# USB.net
KiCad netlist of a schematic drawn in Altium Designer
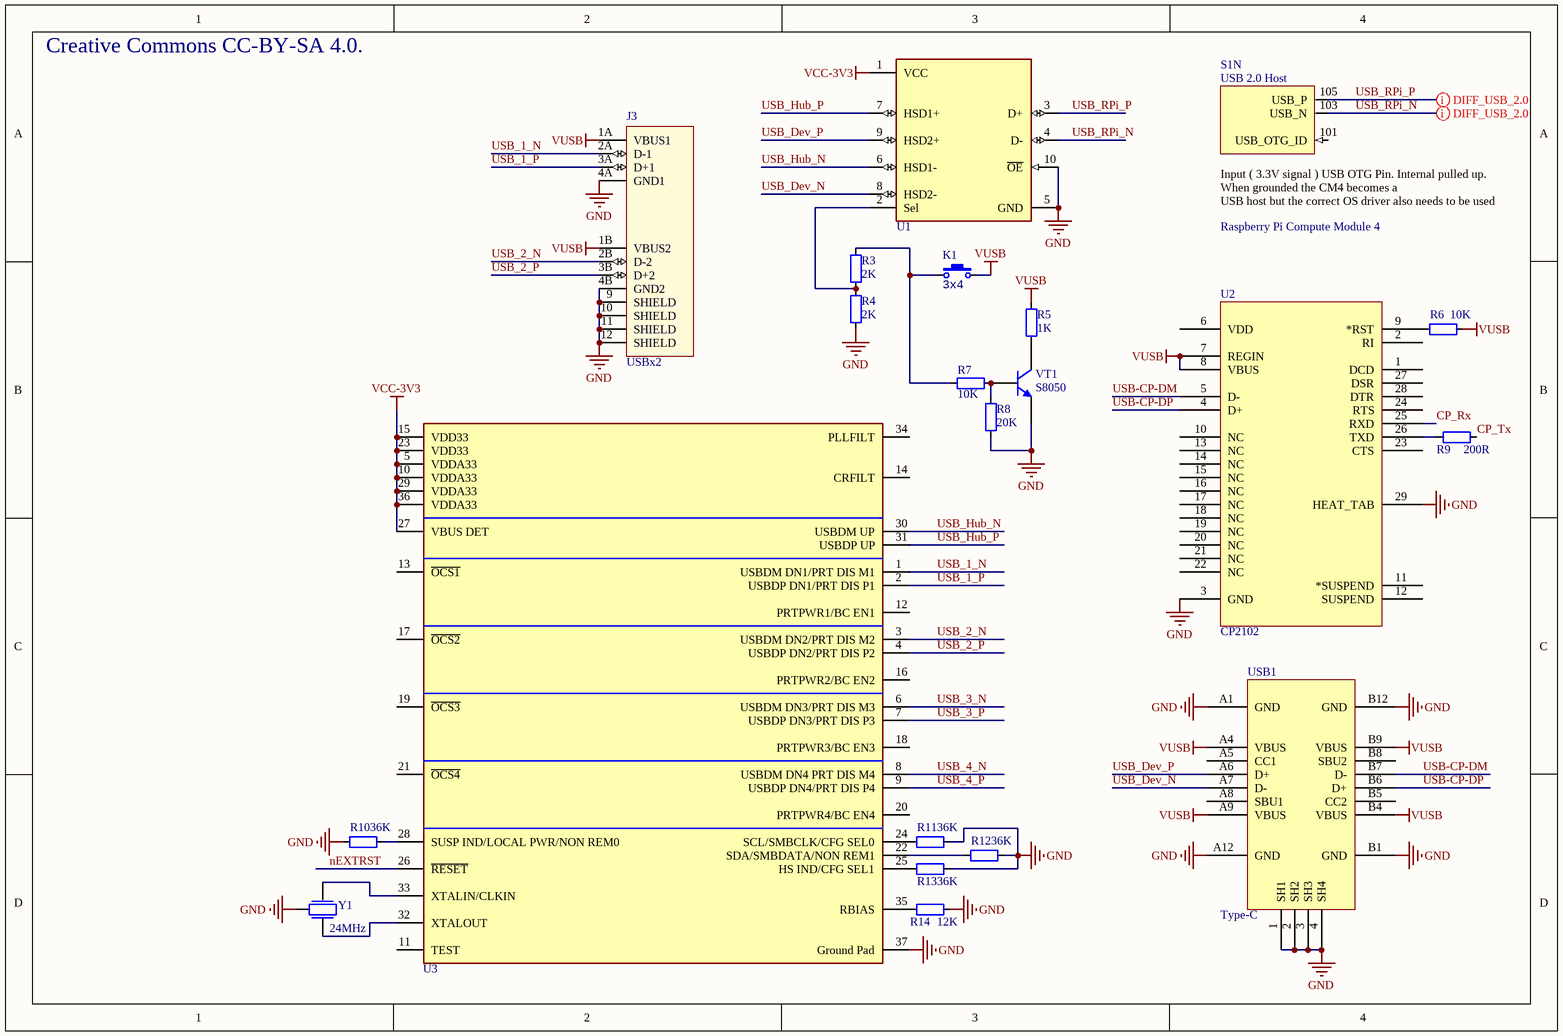
[diagram p0: USB.SchDoc]

(export (version "E")
  (design (tool "Eeschema 10.0.6"))
  (components
    (comp (ref "J3")
      (value "USBx2")
      (footprint "USBx2")
      (description "Usb Conn, Dual Rcpt, 2.0, 2port, 8pos")
      (fields (field (name "MF") "Global Connector Technology") (field (name "MP") "USB1035-GF-P-0-B-B"))
      (libsource (lib "MyPcbLib") (part "USBx2"))
    )
    (comp (ref "K1")
      (value "3x4")
      (footprint "ButtonTACT_3x4x2_180H")
      (description "Button")
      (fields (field (name "Comment") "TACT 2P"))
      (libsource (lib "KitSprout") (part "ButtonTACT_3x4x2_180"))
    )
    (comp (ref "R3")
      (value "2K")
      (footprint "RES_0402")
      (description "Resistor")
      (libsource (lib "MyPcbLib") (part "电阻-0402"))
    )
    (comp (ref "R4")
      (value "2K")
      (footprint "RES_0402")
      (description "Resistor")
      (libsource (lib "MyPcbLib") (part "电阻-0402"))
    )
    (comp (ref "R5")
      (value "1K")
      (footprint "RES_0402")
      (description "Resistor")
      (libsource (lib "MyPcbLib") (part "电阻-0402"))
    )
    (comp (ref "R6")
      (value "10K")
      (footprint "RES_0402")
      (description "Resistor")
      (libsource (lib "") (part "电阻-0402_1"))
    )
    (comp (ref "R7")
      (value "10K")
      (footprint "RES_0402")
      (description "Resistor")
      (libsource (lib "") (part "电阻-0402_2"))
    )
    (comp (ref "R8")
      (value "20K")
      (footprint "RES_0402")
      (description "Resistor")
      (libsource (lib "") (part "电阻-0402_3"))
    )
    (comp (ref "R9")
      (value "200R")
      (footprint "RES_0402")
      (description "Resistor")
      (libsource (lib "") (part "电阻-0402_1"))
    )
    (comp (ref "R10")
      (value "36K")
      (footprint "RES_0402")
      (description "Resistor")
      (libsource (lib "") (part "电阻-0402_1"))
    )
    (comp (ref "R11")
      (value "36K")
      (footprint "RES_0402")
      (description "Resistor")
      (libsource (lib "") (part "电阻-0402_1"))
    )
    (comp (ref "R12")
      (value "36K")
      (footprint "RES_0402")
      (description "Resistor")
      (libsource (lib "") (part "电阻-0402_1"))
    )
    (comp (ref "R13")
      (value "36K")
      (footprint "RES_0402")
      (description "Resistor")
      (libsource (lib "") (part "电阻-0402_1"))
    )
    (comp (ref "R14")
      (value "12K")
      (footprint "RES_0402")
      (description "Resistor")
      (libsource (lib "") (part "电阻-0402_1"))
    )
    (comp (ref "S1")
      (value "Raspberry Pi Compute Module 4")
      (footprint "CM4-F40C-100DS-0.4v_1.5mm_0mm")
      (description "Raspberry Pi Compute Module 4 by Amornthep Phunsin")
      (libsource (lib "SOM") (part "CM4"))
    )
    (comp (ref "U1")
      (value "FSUSB42MUX")
      (footprint "MSOP-10")
      (libsource (lib "MyPcbLib") (part "FSUSB42MUX"))
    )
    (comp (ref "U2")
      (value "CP2102")
      (footprint "QFN-28")
      (description "USB转TTL")
      (libsource (lib "mLib") (part "CP2102"))
    )
    (comp (ref "U3")
      (value "USB2514BT-I-M2")
      (footprint "QFN-36")
      (libsource (lib "MyPcbLib") (part "USB2514BT-I-M2"))
    )
    (comp (ref "USB1")
      (value "Type-C")
      (footprint "Type-C-TOP")
      (libsource (lib "MyPcbLib") (part "USB-Type-C-TOP"))
    )
    (comp (ref "VT1")
      (value "S8050")
      (footprint "SMT_TRIODE_NPN")
      (description "Surface mount NPN transistor, package SOT-23")
      (libsource (lib "MyPcbLib") (part "SMT_TRIODE_NPN"))
    )
    (comp (ref "Y1")
      (value "24MHz")
      (footprint "晶振-3P")
      (description "村田贴片")
      (libsource (lib "MyPcbLib") (part "晶振-3Pin"))
    )
  )
  (nets
    (net (code "1") (name "/CP_Rx") (class "Default")
      (node (ref "U2") (pin "25") (pinfunction "RXD_25") (pintype "passive"))
    )
    (net (code "2") (name "/CP_Tx") (class "Default")
      (node (ref "R9") (pin "1") (pinfunction "1_1") (pintype "passive"))
    )
    (net (code "3") (name "/USB-CP-DM") (class "Default")
      (node (ref "U2") (pin "5") (pinfunction "D-_5") (pintype "passive"))
      (node (ref "USB1") (pin "B7") (pinfunction "D-_B7") (pintype "passive"))
    )
    (net (code "4") (name "/USB-CP-DP") (class "Default")
      (node (ref "U2") (pin "4") (pinfunction "D+_4") (pintype "passive"))
      (node (ref "USB1") (pin "B6") (pinfunction "D+_B6") (pintype "passive"))
    )
    (net (code "5") (name "/USB_1_N") (class "Default")
      (node (ref "J3") (pin "2A") (pinfunction "D-1_2A") (pintype "bidirectional"))
      (node (ref "U3") (pin "1") (pinfunction "USBDM_DN1/PRT_DIS_M1_1") (pintype "passive"))
    )
    (net (code "6") (name "/USB_1_P") (class "Default")
      (node (ref "J3") (pin "3A") (pinfunction "D+1_3A") (pintype "bidirectional"))
      (node (ref "U3") (pin "2") (pinfunction "USBDP_DN1/PRT_DIS_P1_2") (pintype "passive"))
    )
    (net (code "7") (name "/USB_2_N") (class "Default")
      (node (ref "J3") (pin "2B") (pinfunction "D-2_2B") (pintype "bidirectional"))
      (node (ref "U3") (pin "3") (pinfunction "USBDM_DN2/PRT_DIS_M2_3") (pintype "passive"))
    )
    (net (code "8") (name "/USB_2_P") (class "Default")
      (node (ref "J3") (pin "3B") (pinfunction "D+2_3B") (pintype "bidirectional"))
      (node (ref "U3") (pin "4") (pinfunction "USBDP_DN2/PRT_DIS_P2_4") (pintype "passive"))
    )
    (net (code "9") (name "/USB_3_N") (class "Default")
      (node (ref "U3") (pin "6") (pinfunction "USBDM_DN3/PRT_DIS_M3_6") (pintype "passive"))
    )
    (net (code "10") (name "/USB_3_P") (class "Default")
      (node (ref "U3") (pin "7") (pinfunction "USBDP_DN3/PRT_DIS_P3_7") (pintype "passive"))
    )
    (net (code "11") (name "/USB_4_N") (class "Default")
      (node (ref "U3") (pin "8") (pinfunction "USBDM_DN4_PRT_DIS_M4_8") (pintype "passive"))
    )
    (net (code "12") (name "/USB_4_P") (class "Default")
      (node (ref "U3") (pin "9") (pinfunction "USBDP_DN4/PRT_DIS_P4_9") (pintype "passive"))
    )
    (net (code "13") (name "/USB_Dev_N") (class "Default")
      (node (ref "U1") (pin "8") (pinfunction "HSD2-_8") (pintype "bidirectional"))
      (node (ref "USB1") (pin "A7") (pinfunction "D-_A7") (pintype "passive"))
    )
    (net (code "14") (name "/USB_Dev_P") (class "Default")
      (node (ref "U1") (pin "9") (pinfunction "HSD2+_9") (pintype "bidirectional"))
      (node (ref "USB1") (pin "A6") (pinfunction "D+_A6") (pintype "passive"))
    )
    (net (code "15") (name "/USB_Hub_N") (class "Default")
      (node (ref "U1") (pin "6") (pinfunction "HSD1-_6") (pintype "bidirectional"))
      (node (ref "U3") (pin "30") (pinfunction "USBDM_UP_30") (pintype "passive"))
    )
    (net (code "16") (name "/USB_Hub_P") (class "Default")
      (node (ref "U1") (pin "7") (pinfunction "HSD1+_7") (pintype "bidirectional"))
      (node (ref "U3") (pin "31") (pinfunction "USBDP_UP_31") (pintype "passive"))
    )
    (net (code "17") (name "/USB_RPi_N") (class "Default")
      (node (ref "S1") (pin "103") (pinfunction "USB_N_103") (pintype "passive"))
      (node (ref "U1") (pin "4") (pinfunction "D-_4") (pintype "bidirectional"))
    )
    (net (code "18") (name "/USB_RPi_P") (class "Default")
      (node (ref "S1") (pin "105") (pinfunction "USB_P_105") (pintype "passive"))
      (node (ref "U1") (pin "3") (pinfunction "D+_3") (pintype "bidirectional"))
    )
    (net (code "19") (name "/nEXTRST") (class "Default")
      (node (ref "U3") (pin "26") (pinfunction "~{RESET}_26") (pintype "passive"))
    )
    (net (code "20") (name "GND") (class "Default")
      (node (ref "J3") (pin "10") (pinfunction "SHIELD_10") (pintype "power_in"))
      (node (ref "J3") (pin "11") (pinfunction "SHIELD_11") (pintype "power_in"))
      (node (ref "J3") (pin "12") (pinfunction "SHIELD_12") (pintype "power_in"))
      (node (ref "J3") (pin "4A") (pinfunction "GND1_4A") (pintype "power_in"))
      (node (ref "J3") (pin "4B") (pinfunction "GND2_4B") (pintype "power_in"))
      (node (ref "J3") (pin "9") (pinfunction "SHIELD_9") (pintype "power_in"))
      (node (ref "R10") (pin "2") (pinfunction "2_2") (pintype "passive"))
      (node (ref "R11") (pin "1") (pinfunction "1_1") (pintype "passive"))
      (node (ref "R12") (pin "1") (pinfunction "1_1") (pintype "passive"))
      (node (ref "R13") (pin "1") (pinfunction "1_1") (pintype "passive"))
      (node (ref "R14") (pin "1") (pinfunction "1_1") (pintype "passive"))
      (node (ref "R4") (pin "2") (pinfunction "2_2") (pintype "passive"))
      (node (ref "R8") (pin "1") (pinfunction "1_1") (pintype "passive"))
      (node (ref "U1") (pin "10") (pinfunction "~{OE}_10") (pintype "input"))
      (node (ref "U1") (pin "5") (pinfunction "GND_5") (pintype "power_in"))
      (node (ref "U2") (pin "29") (pinfunction "HEAT_TAB_29") (pintype "passive"))
      (node (ref "U2") (pin "3") (pinfunction "GND_3") (pintype "passive"))
      (node (ref "U3") (pin "37") (pinfunction "Ground_Pad_37") (pintype "passive"))
      (node (ref "USB1") (pin "1") (pinfunction "SH1_1") (pintype "passive"))
      (node (ref "USB1") (pin "2") (pinfunction "SH2_2") (pintype "passive"))
      (node (ref "USB1") (pin "3") (pinfunction "SH3_3") (pintype "passive"))
      (node (ref "USB1") (pin "4") (pinfunction "SH4_4") (pintype "passive"))
      (node (ref "USB1") (pin "A1") (pinfunction "GND_A1") (pintype "passive"))
      (node (ref "USB1") (pin "A12") (pinfunction "GND_A12") (pintype "passive"))
      (node (ref "USB1") (pin "B1") (pinfunction "GND_B1") (pintype "passive"))
      (node (ref "USB1") (pin "B12") (pinfunction "GND_B12") (pintype "passive"))
      (node (ref "VT1") (pin "2") (pinfunction "E_2") (pintype "passive"))
      (node (ref "Y1") (pin "2") (pinfunction "2_2") (pintype "passive"))
    )
    (net (code "21") (name "Net-(K1-Pad1)") (class "Default")
      (node (ref "K1") (pin "1") (pinfunction "1_1") (pintype "passive"))
      (node (ref "R3") (pin "1") (pinfunction "1_1") (pintype "passive"))
      (node (ref "R7") (pin "1") (pinfunction "1_1") (pintype "passive"))
    )
    (net (code "22") (name "Net-(U1-Sel)") (class "Default")
      (node (ref "R3") (pin "2") (pinfunction "2_2") (pintype "passive"))
      (node (ref "R4") (pin "1") (pinfunction "1_1") (pintype "passive"))
      (node (ref "U1") (pin "2") (pinfunction "Sel_2") (pintype "passive"))
    )
    (net (code "23") (name "Net-(U2-*RST)") (class "Default")
      (node (ref "R6") (pin "2") (pinfunction "2_2") (pintype "passive"))
      (node (ref "U2") (pin "9") (pinfunction "*RST_9") (pintype "passive"))
    )
    (net (code "24") (name "Net-(U2-TXD)") (class "Default")
      (node (ref "R9") (pin "2") (pinfunction "2_2") (pintype "passive"))
      (node (ref "U2") (pin "26") (pinfunction "TXD_26") (pintype "passive"))
    )
    (net (code "25") (name "Net-(U3-HS_IND{slash}CFG_SEL1)") (class "Default")
      (node (ref "R13") (pin "2") (pinfunction "2_2") (pintype "passive"))
      (node (ref "U3") (pin "25") (pinfunction "HS_IND/CFG_SEL1_25") (pintype "passive"))
    )
    (net (code "26") (name "Net-(U3-RBIAS)") (class "Default")
      (node (ref "R14") (pin "2") (pinfunction "2_2") (pintype "passive"))
      (node (ref "U3") (pin "35") (pinfunction "RBIAS_35") (pintype "passive"))
    )
    (net (code "27") (name "Net-(U3-SCL{slash}SMBCLK{slash}CFG_SEL0)") (class "Default")
      (node (ref "R11") (pin "2") (pinfunction "2_2") (pintype "passive"))
      (node (ref "U3") (pin "24") (pinfunction "SCL/SMBCLK/CFG_SEL0_24") (pintype "passive"))
    )
    (net (code "28") (name "Net-(U3-SDA{slash}SMBDATA{slash}NON_REM1)") (class "Default")
      (node (ref "R12") (pin "2") (pinfunction "2_2") (pintype "passive"))
      (node (ref "U3") (pin "22") (pinfunction "SDA/SMBDATA/NON_REM1_22") (pintype "passive"))
    )
    (net (code "29") (name "Net-(U3-SUSP_IND{slash}LOCAL_PWR{slash}NON_REM0)") (class "Default")
      (node (ref "R10") (pin "1") (pinfunction "1_1") (pintype "passive"))
      (node (ref "U3") (pin "28") (pinfunction "SUSP_IND/LOCAL_PWR/NON_REM0_28") (pintype "passive"))
    )
    (net (code "30") (name "Net-(U3-XTALIN{slash}CLKIN)") (class "Default")
      (node (ref "U3") (pin "33") (pinfunction "XTALIN/CLKIN_33") (pintype "passive"))
      (node (ref "Y1") (pin "3") (pinfunction "3_3") (pintype "passive"))
    )
    (net (code "31") (name "Net-(U3-XTALOUT)") (class "Default")
      (node (ref "U3") (pin "32") (pinfunction "XTALOUT_32") (pintype "passive"))
      (node (ref "Y1") (pin "1") (pinfunction "1_1") (pintype "passive"))
    )
    (net (code "32") (name "Net-(VT1-B)") (class "Default")
      (node (ref "R7") (pin "2") (pinfunction "2_2") (pintype "passive"))
      (node (ref "R8") (pin "2") (pinfunction "2_2") (pintype "passive"))
      (node (ref "VT1") (pin "1") (pinfunction "B_1") (pintype "passive"))
    )
    (net (code "33") (name "Net-(VT1-C)") (class "Default")
      (node (ref "R5") (pin "2") (pinfunction "2_2") (pintype "passive"))
      (node (ref "VT1") (pin "3") (pinfunction "C_3") (pintype "passive"))
    )
    (net (code "34") (name "VCC-3V3") (class "Default")
      (node (ref "U1") (pin "1") (pinfunction "VCC_1") (pintype "power_in"))
      (node (ref "U3") (pin "10") (pinfunction "VDDA33_10") (pintype "passive"))
      (node (ref "U3") (pin "15") (pinfunction "VDD33_15") (pintype "passive"))
      (node (ref "U3") (pin "23") (pinfunction "VDD33_23") (pintype "passive"))
      (node (ref "U3") (pin "27") (pinfunction "VBUS_DET_27") (pintype "passive"))
      (node (ref "U3") (pin "29") (pinfunction "VDDA33_29") (pintype "passive"))
      (node (ref "U3") (pin "36") (pinfunction "VDDA33_36") (pintype "passive"))
      (node (ref "U3") (pin "5") (pinfunction "VDDA33_5") (pintype "passive"))
    )
    (net (code "35") (name "VUSB") (class "Default")
      (node (ref "J3") (pin "1A") (pinfunction "VBUS1_1A") (pintype "power_in"))
      (node (ref "J3") (pin "1B") (pinfunction "VBUS2_1B") (pintype "power_in"))
      (node (ref "K1") (pin "2") (pinfunction "2_2") (pintype "passive"))
      (node (ref "R5") (pin "1") (pinfunction "1_1") (pintype "passive"))
      (node (ref "R6") (pin "1") (pinfunction "1_1") (pintype "passive"))
      (node (ref "U2") (pin "7") (pinfunction "REGIN_7") (pintype "passive"))
      (node (ref "U2") (pin "8") (pinfunction "VBUS_8") (pintype "passive"))
      (node (ref "USB1") (pin "A4") (pinfunction "VBUS_A4") (pintype "passive"))
      (node (ref "USB1") (pin "A9") (pinfunction "VBUS_A9") (pintype "passive"))
      (node (ref "USB1") (pin "B4") (pinfunction "VBUS_B4") (pintype "passive"))
      (node (ref "USB1") (pin "B9") (pinfunction "VBUS_B9") (pintype "passive"))
    )
    (net (code "36") (name "unconnected-(S1N-USB_OTG_ID-Pad101)") (class "Default")
      (node (ref "S1") (pin "101") (pinfunction "USB_OTG_ID_101") (pintype "input"))
    )
    (net (code "37") (name "unconnected-(U2-*SUSPEND-Pad11)") (class "Default")
      (node (ref "U2") (pin "11") (pinfunction "*SUSPEND_11") (pintype "passive"))
    )
    (net (code "38") (name "unconnected-(U2-CTS-Pad23)") (class "Default")
      (node (ref "U2") (pin "23") (pinfunction "CTS_23") (pintype "passive"))
    )
    (net (code "39") (name "unconnected-(U2-DCD-Pad1)") (class "Default")
      (node (ref "U2") (pin "1") (pinfunction "DCD_1") (pintype "passive"))
    )
    (net (code "40") (name "unconnected-(U2-DSR-Pad27)") (class "Default")
      (node (ref "U2") (pin "27") (pinfunction "DSR_27") (pintype "passive"))
    )
    (net (code "41") (name "unconnected-(U2-DTR-Pad28)") (class "Default")
      (node (ref "U2") (pin "28") (pinfunction "DTR_28") (pintype "passive"))
    )
    (net (code "42") (name "unconnected-(U2-NC-Pad10)") (class "Default")
      (node (ref "U2") (pin "10") (pinfunction "NC_10") (pintype "passive"))
    )
    (net (code "43") (name "unconnected-(U2-NC-Pad13)") (class "Default")
      (node (ref "U2") (pin "13") (pinfunction "NC_13") (pintype "passive"))
    )
    (net (code "44") (name "unconnected-(U2-NC-Pad14)") (class "Default")
      (node (ref "U2") (pin "14") (pinfunction "NC_14") (pintype "passive"))
    )
    (net (code "45") (name "unconnected-(U2-NC-Pad15)") (class "Default")
      (node (ref "U2") (pin "15") (pinfunction "NC_15") (pintype "passive"))
    )
    (net (code "46") (name "unconnected-(U2-NC-Pad16)") (class "Default")
      (node (ref "U2") (pin "16") (pinfunction "NC_16") (pintype "passive"))
    )
    (net (code "47") (name "unconnected-(U2-NC-Pad17)") (class "Default")
      (node (ref "U2") (pin "17") (pinfunction "NC_17") (pintype "passive"))
    )
    (net (code "48") (name "unconnected-(U2-NC-Pad18)") (class "Default")
      (node (ref "U2") (pin "18") (pinfunction "NC_18") (pintype "passive"))
    )
    (net (code "49") (name "unconnected-(U2-NC-Pad19)") (class "Default")
      (node (ref "U2") (pin "19") (pinfunction "NC_19") (pintype "passive"))
    )
    (net (code "50") (name "unconnected-(U2-NC-Pad20)") (class "Default")
      (node (ref "U2") (pin "20") (pinfunction "NC_20") (pintype "passive"))
    )
    (net (code "51") (name "unconnected-(U2-NC-Pad21)") (class "Default")
      (node (ref "U2") (pin "21") (pinfunction "NC_21") (pintype "passive"))
    )
    (net (code "52") (name "unconnected-(U2-NC-Pad22)") (class "Default")
      (node (ref "U2") (pin "22") (pinfunction "NC_22") (pintype "passive"))
    )
    (net (code "53") (name "unconnected-(U2-RI-Pad2)") (class "Default")
      (node (ref "U2") (pin "2") (pinfunction "RI_2") (pintype "passive"))
    )
    (net (code "54") (name "unconnected-(U2-RTS-Pad24)") (class "Default")
      (node (ref "U2") (pin "24") (pinfunction "RTS_24") (pintype "passive"))
    )
    (net (code "55") (name "unconnected-(U2-SUSPEND-Pad12)") (class "Default")
      (node (ref "U2") (pin "12") (pinfunction "SUSPEND_12") (pintype "passive"))
    )
    (net (code "56") (name "unconnected-(U2-VDD-Pad6)") (class "Default")
      (node (ref "U2") (pin "6") (pinfunction "VDD_6") (pintype "passive"))
    )
    (net (code "57") (name "unconnected-(U3-CRFILT-Pad14)") (class "Default")
      (node (ref "U3") (pin "14") (pinfunction "CRFILT_14") (pintype "passive"))
    )
    (net (code "58") (name "unconnected-(U3-PLLFILT-Pad34)") (class "Default")
      (node (ref "U3") (pin "34") (pinfunction "PLLFILT_34") (pintype "passive"))
    )
    (net (code "59") (name "unconnected-(U3-PRTPWR1{slash}BC_EN1-Pad12)") (class "Default")
      (node (ref "U3") (pin "12") (pinfunction "PRTPWR1/BC_EN1_12") (pintype "passive"))
    )
    (net (code "60") (name "unconnected-(U3-PRTPWR2{slash}BC_EN2-Pad16)") (class "Default")
      (node (ref "U3") (pin "16") (pinfunction "PRTPWR2/BC_EN2_16") (pintype "passive"))
    )
    (net (code "61") (name "unconnected-(U3-PRTPWR3{slash}BC_EN3-Pad18)") (class "Default")
      (node (ref "U3") (pin "18") (pinfunction "PRTPWR3/BC_EN3_18") (pintype "passive"))
    )
    (net (code "62") (name "unconnected-(U3-PRTPWR4{slash}BC_EN4-Pad20)") (class "Default")
      (node (ref "U3") (pin "20") (pinfunction "PRTPWR4/BC_EN4_20") (pintype "passive"))
    )
    (net (code "63") (name "unconnected-(U3-TEST-Pad11)") (class "Default")
      (node (ref "U3") (pin "11") (pinfunction "TEST_11") (pintype "passive"))
    )
    (net (code "64") (name "unconnected-(U3-~{OCS1}-Pad13)") (class "Default")
      (node (ref "U3") (pin "13") (pinfunction "~{OCS1}_13") (pintype "passive"))
    )
    (net (code "65") (name "unconnected-(U3-~{OCS2}-Pad17)") (class "Default")
      (node (ref "U3") (pin "17") (pinfunction "~{OCS2}_17") (pintype "passive"))
    )
    (net (code "66") (name "unconnected-(U3-~{OCS3}-Pad19)") (class "Default")
      (node (ref "U3") (pin "19") (pinfunction "~{OCS3}_19") (pintype "passive"))
    )
    (net (code "67") (name "unconnected-(U3-~{OCS4}-Pad21)") (class "Default")
      (node (ref "U3") (pin "21") (pinfunction "~{OCS4}_21") (pintype "passive"))
    )
    (net (code "68") (name "unconnected-(USB1-CC1-PadA5)") (class "Default")
      (node (ref "USB1") (pin "A5") (pinfunction "CC1_A5") (pintype "passive"))
    )
    (net (code "69") (name "unconnected-(USB1-CC2-PadB5)") (class "Default")
      (node (ref "USB1") (pin "B5") (pinfunction "CC2_B5") (pintype "passive"))
    )
    (net (code "70") (name "unconnected-(USB1-SBU1-PadA8)") (class "Default")
      (node (ref "USB1") (pin "A8") (pinfunction "SBU1_A8") (pintype "passive"))
    )
    (net (code "71") (name "unconnected-(USB1-SBU2-PadB8)") (class "Default")
      (node (ref "USB1") (pin "B8") (pinfunction "SBU2_B8") (pintype "passive"))
    )
  )
)
